# 05_Pressure_and_LoadCell.net
KiCad netlist of a schematic drawn in Altium Designer
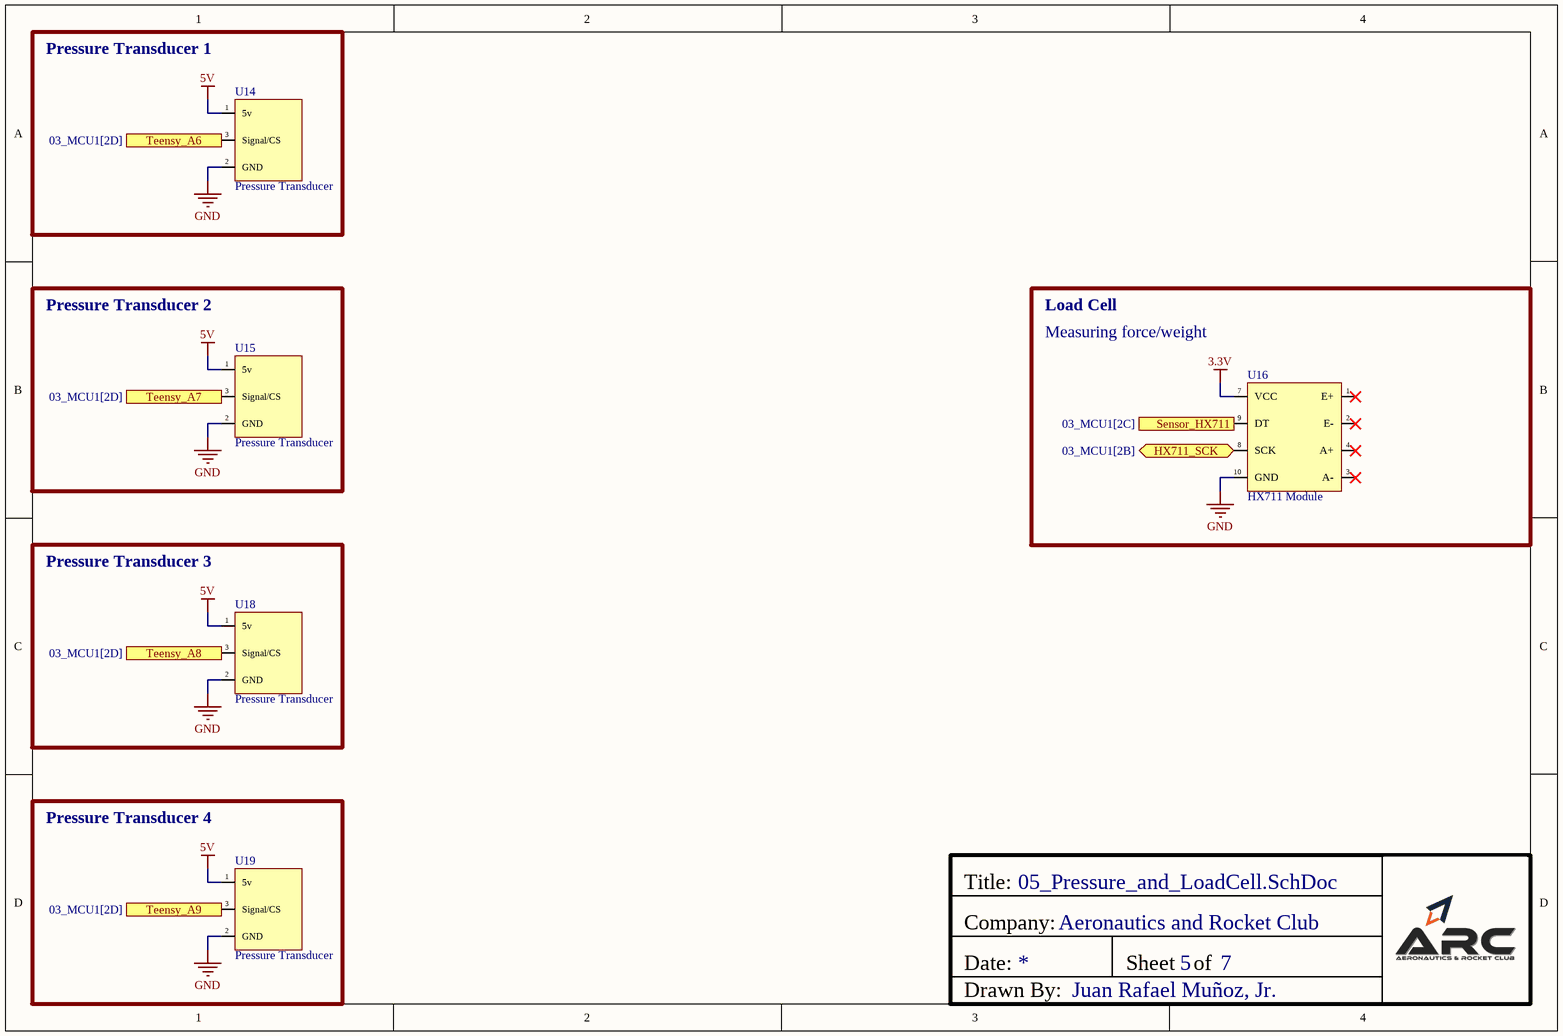
[diagram p0: 05_Pressure_and_LoadCell.SchDoc]

(export (version "E")
  (design (tool "Eeschema 10.0.6"))
  (components
    (comp (ref "U14")
      (value "Pressure Transducer")
      (footprint "3-PIN AVIATION CONNECTOR")
      (libsource (lib "Ground Support_Schlib") (part "Pressure Transducer"))
    )
    (comp (ref "U15")
      (value "Pressure Transducer")
      (footprint "3-PIN AVIATION CONNECTOR")
      (libsource (lib "Ground Support_Schlib") (part "Pressure Transducer"))
    )
    (comp (ref "U16")
      (value "HX711 Module")
      (footprint "HX711 Module")
      (libsource (lib "Ground Support_Schlib") (part "HX711 Module"))
    )
    (comp (ref "U18")
      (value "Pressure Transducer")
      (footprint "3-PIN AVIATION CONNECTOR")
      (libsource (lib "Ground Support_Schlib") (part "Pressure Transducer"))
    )
    (comp (ref "U19")
      (value "Pressure Transducer")
      (footprint "3-PIN AVIATION CONNECTOR")
      (libsource (lib "Ground Support_Schlib") (part "Pressure Transducer"))
    )
  )
  (nets
    (net (code "1") (name "/HX711_SCK") (class "Default")
      (node (ref "U16") (pin "8") (pinfunction "SCK_8") (pintype "passive"))
    )
    (net (code "2") (name "/Sensor_HX711") (class "Default")
      (node (ref "U16") (pin "9") (pinfunction "DT_9") (pintype "passive"))
    )
    (net (code "3") (name "/Teensy_A6") (class "Default")
      (node (ref "U14") (pin "3") (pinfunction "Signal/CS_3") (pintype "passive"))
    )
    (net (code "4") (name "/Teensy_A7") (class "Default")
      (node (ref "U15") (pin "3") (pinfunction "Signal/CS_3") (pintype "passive"))
    )
    (net (code "5") (name "/Teensy_A8") (class "Default")
      (node (ref "U18") (pin "3") (pinfunction "Signal/CS_3") (pintype "passive"))
    )
    (net (code "6") (name "/Teensy_A9") (class "Default")
      (node (ref "U19") (pin "3") (pinfunction "Signal/CS_3") (pintype "passive"))
    )
    (net (code "7") (name "3.3V") (class "Default")
      (node (ref "U16") (pin "7") (pinfunction "VCC_7") (pintype "power_in"))
    )
    (net (code "8") (name "5V") (class "Default")
      (node (ref "U14") (pin "1") (pinfunction "5v_1") (pintype "power_in"))
      (node (ref "U15") (pin "1") (pinfunction "5v_1") (pintype "power_in"))
      (node (ref "U18") (pin "1") (pinfunction "5v_1") (pintype "power_in"))
      (node (ref "U19") (pin "1") (pinfunction "5v_1") (pintype "power_in"))
    )
    (net (code "9") (name "GND") (class "Default")
      (node (ref "U14") (pin "2") (pinfunction "GND_2") (pintype "power_in"))
      (node (ref "U15") (pin "2") (pinfunction "GND_2") (pintype "power_in"))
      (node (ref "U16") (pin "10") (pinfunction "GND_10") (pintype "power_in"))
      (node (ref "U18") (pin "2") (pinfunction "GND_2") (pintype "power_in"))
      (node (ref "U19") (pin "2") (pinfunction "GND_2") (pintype "power_in"))
    )
    (net (code "10") (name "unconnected-(U16-A+-Pad4)") (class "Default")
      (node (ref "U16") (pin "4") (pinfunction "A+_4") (pintype "passive+no_connect"))
    )
    (net (code "11") (name "unconnected-(U16-A--Pad3)") (class "Default")
      (node (ref "U16") (pin "3") (pinfunction "A-_3") (pintype "passive+no_connect"))
    )
    (net (code "12") (name "unconnected-(U16-E+-Pad1)") (class "Default")
      (node (ref "U16") (pin "1") (pinfunction "E+_1") (pintype "passive+no_connect"))
    )
    (net (code "13") (name "unconnected-(U16-E--Pad2)") (class "Default")
      (node (ref "U16") (pin "2") (pinfunction "E-_2") (pintype "passive+no_connect"))
    )
  )
)
